# pag7936.net
KiCad netlist of a schematic drawn in Altium Designer
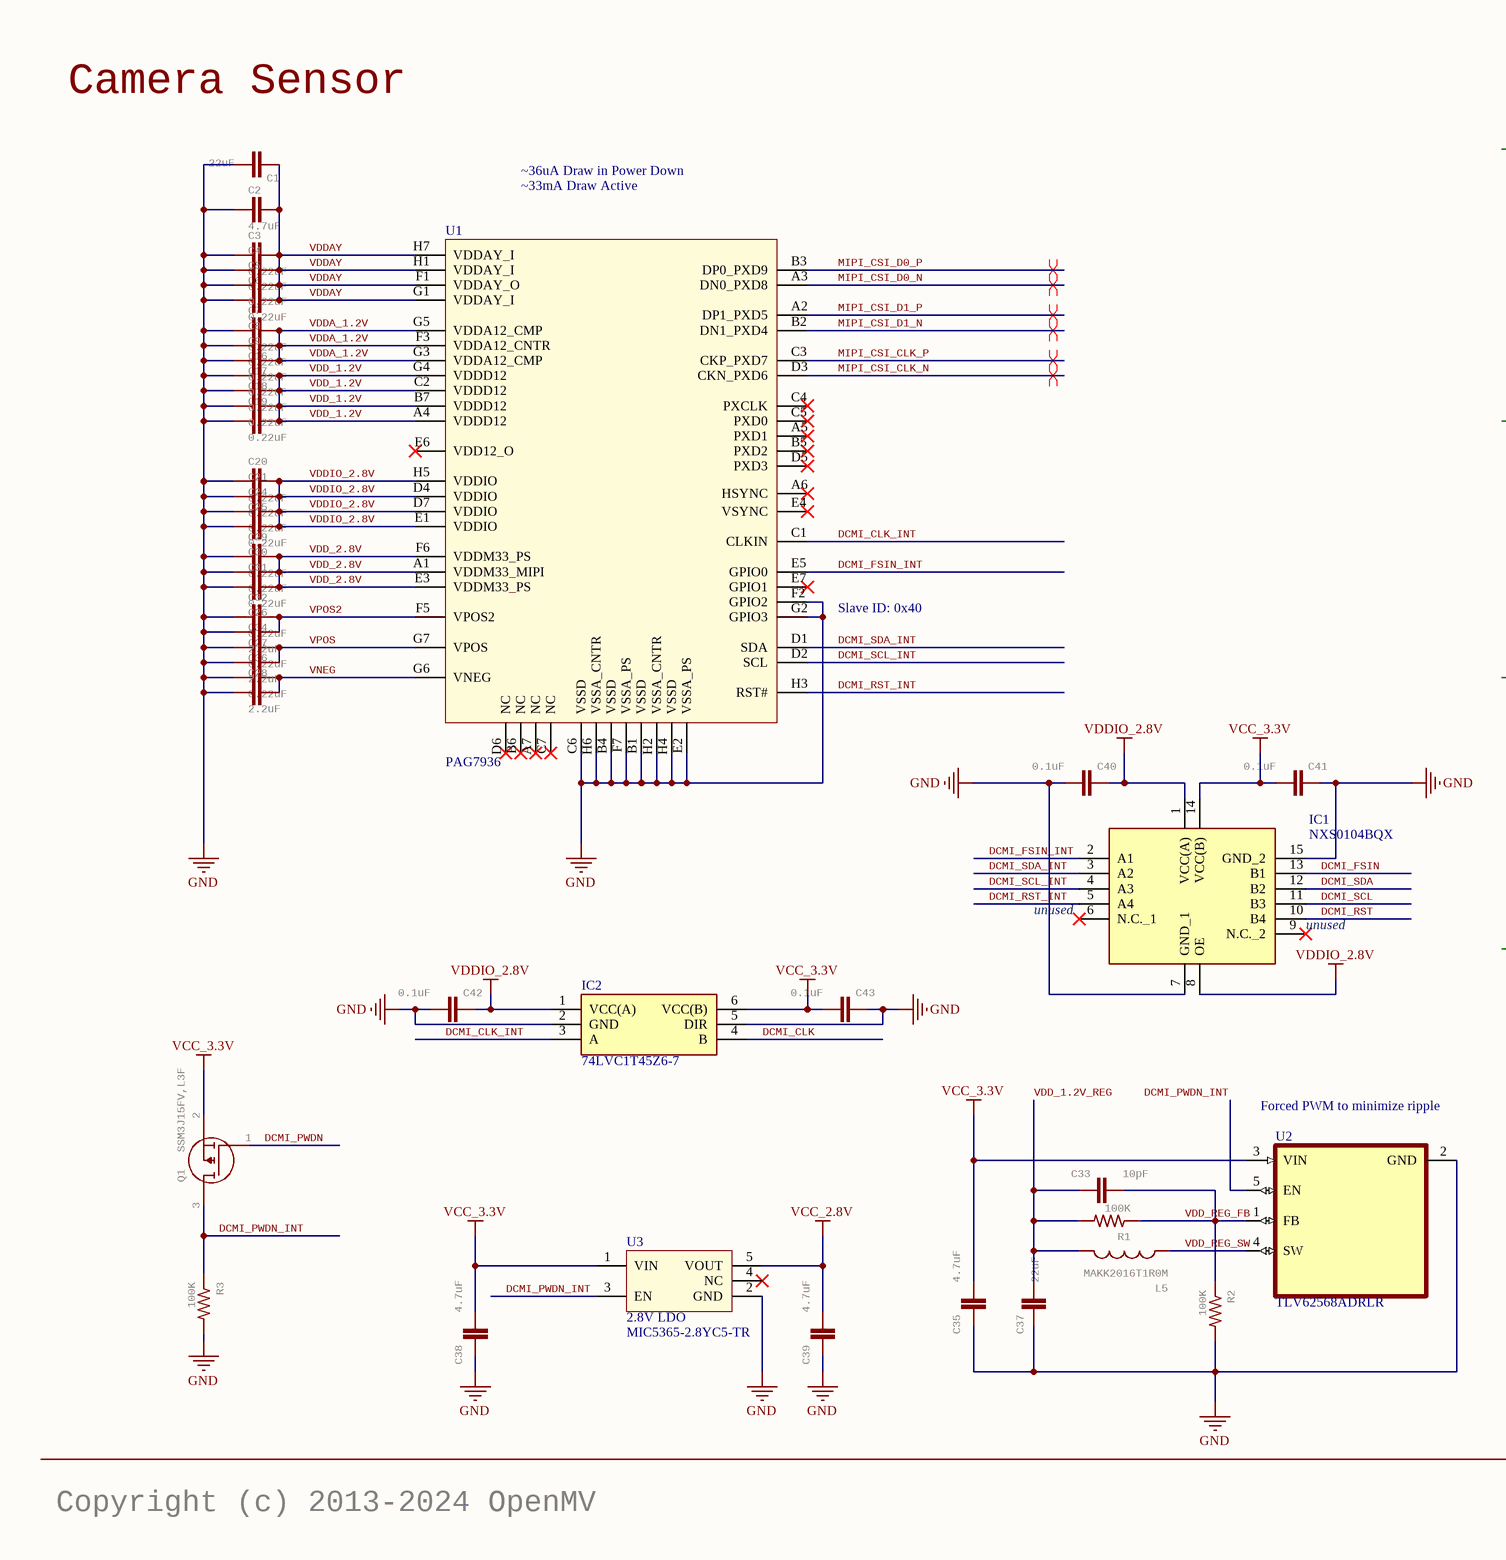
[diagram p0: pag7936.SchDoc, left]
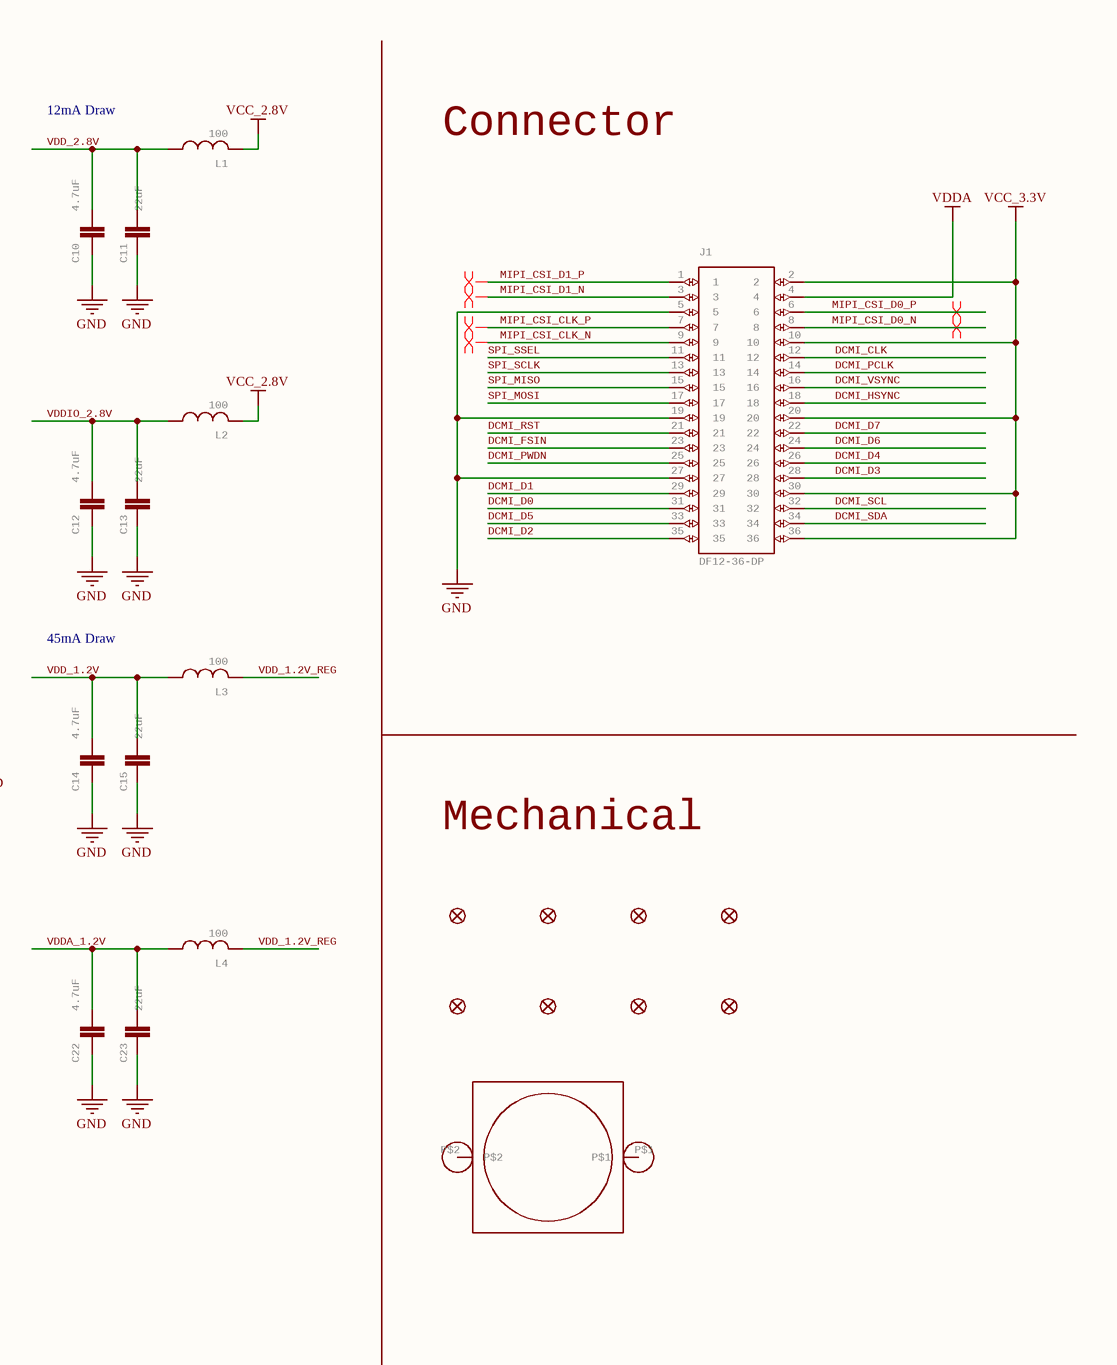
[diagram p1: pag7936.SchDoc, right]

(export (version "E")
  (design (tool "Eeschema 10.0.6"))
  (components
    (comp (ref "C1")
      (value "22uF")
      (footprint "0805")
      (fields (field (name "MPN") "CL21A226MQQNNNE"))
      (libsource (lib "") (part "22UF-0805-6.3V-20%_1"))
    )
    (comp (ref "C2")
      (value "4.7uF")
      (footprint "0402-CAP")
      (description "CapacitorStandard 0603 ceramic capacitor, and 0.1\" leaded capacitor.")
      (fields (field (name "MPN") "JMK105BBJ475MV-F"))
      (libsource (lib "openmv-ae3-r2") (part "CAP0402-CAP"))
    )
    (comp (ref "C3")
      (value "0.22uF")
      (footprint "C0201")
      (description "CAPACITOR, European symbol")
      (fields (field (name "MPN") "GRM033R60J224ME15D"))
      (libsource (lib "openmv-ae3-r2") (part "C-EUC0201"))
    )
    (comp (ref "C4")
      (value "0.22uF")
      (footprint "C0201")
      (description "CAPACITOR, European symbol")
      (fields (field (name "MPN") "GRM033R60J224ME15D"))
      (libsource (lib "openmv-ae3-r2") (part "C-EUC0201"))
    )
    (comp (ref "C5")
      (value "0.22uF")
      (footprint "C0201")
      (description "CAPACITOR, European symbol")
      (fields (field (name "MPN") "GRM033R60J224ME15D"))
      (libsource (lib "openmv-ae3-r2") (part "C-EUC0201"))
    )
    (comp (ref "C6")
      (value "0.22uF")
      (footprint "C0201")
      (description "CAPACITOR, European symbol")
      (fields (field (name "MPN") "GRM033R60J224ME15D"))
      (libsource (lib "openmv-ae3-r2") (part "C-EUC0201"))
    )
    (comp (ref "C7")
      (value "0.22uF")
      (footprint "C0201")
      (description "CAPACITOR, European symbol")
      (fields (field (name "MPN") "GRM033R60J224ME15D"))
      (libsource (lib "openmv-ae3-r2") (part "C-EUC0201"))
    )
    (comp (ref "C8")
      (value "0.22uF")
      (footprint "C0201")
      (description "CAPACITOR, European symbol")
      (fields (field (name "MPN") "GRM033R60J224ME15D"))
      (libsource (lib "openmv-ae3-r2") (part "C-EUC0201"))
    )
    (comp (ref "C9")
      (value "0.22uF")
      (footprint "C0201")
      (description "CAPACITOR, European symbol")
      (fields (field (name "MPN") "GRM033R60J224ME15D"))
      (libsource (lib "openmv-ae3-r2") (part "C-EUC0201"))
    )
    (comp (ref "C10")
      (value "4.7uF")
      (footprint "0402-CAP")
      (description "0402 (1005 Metric) Nick Garner - TeleSense")
      (fields (field (name "MPN") "JMK105BBJ475MV-F"))
      (libsource (lib "camera-modules") (part "CAP_0402"))
    )
    (comp (ref "C11")
      (value "22uF")
      (footprint "0805")
      (fields (field (name "MPN") "CL21A226MQQNNNE"))
      (libsource (lib "camera-modules") (part "22UF-0805-6.3V-20%"))
    )
    (comp (ref "C12")
      (value "4.7uF")
      (footprint "0402-CAP")
      (description "0402 (1005 Metric) Nick Garner - TeleSense")
      (fields (field (name "MPN") "JMK105BBJ475MV-F"))
      (libsource (lib "camera-modules") (part "CAP_0402"))
    )
    (comp (ref "C13")
      (value "22uF")
      (footprint "0805")
      (fields (field (name "MPN") "CL21A226MQQNNNE"))
      (libsource (lib "camera-modules") (part "22UF-0805-6.3V-20%"))
    )
    (comp (ref "C14")
      (value "4.7uF")
      (footprint "0402-CAP")
      (description "0402 (1005 Metric) Nick Garner - TeleSense")
      (fields (field (name "MPN") "JMK105BBJ475MV-F"))
      (libsource (lib "camera-modules") (part "CAP_0402"))
    )
    (comp (ref "C15")
      (value "22uF")
      (footprint "0805")
      (fields (field (name "MPN") "CL21A226MQQNNNE"))
      (libsource (lib "camera-modules") (part "22UF-0805-6.3V-20%"))
    )
    (comp (ref "C16")
      (value "0.22uF")
      (footprint "C0201")
      (description "CAPACITOR, European symbol")
      (fields (field (name "MPN") "GRM033R60J224ME15D"))
      (libsource (lib "openmv-ae3-r2") (part "C-EUC0201"))
    )
    (comp (ref "C17")
      (value "0.22uF")
      (footprint "C0201")
      (description "CAPACITOR, European symbol")
      (fields (field (name "MPN") "GRM033R60J224ME15D"))
      (libsource (lib "openmv-ae3-r2") (part "C-EUC0201"))
    )
    (comp (ref "C18")
      (value "0.22uF")
      (footprint "C0201")
      (description "CAPACITOR, European symbol")
      (fields (field (name "MPN") "GRM033R60J224ME15D"))
      (libsource (lib "openmv-ae3-r2") (part "C-EUC0201"))
    )
    (comp (ref "C19")
      (value "0.22uF")
      (footprint "C0201")
      (description "CAPACITOR, European symbol")
      (fields (field (name "MPN") "GRM033R60J224ME15D"))
      (libsource (lib "openmv-ae3-r2") (part "C-EUC0201"))
    )
    (comp (ref "C20")
      (value "0.22uF")
      (footprint "C0201")
      (description "CAPACITOR, European symbol")
      (fields (field (name "MPN") "GRM033R60J224ME15D"))
      (libsource (lib "openmv-ae3-r2") (part "C-EUC0201"))
    )
    (comp (ref "C21")
      (value "0.22uF")
      (footprint "C0201")
      (description "CAPACITOR, European symbol")
      (fields (field (name "MPN") "GRM033R60J224ME15D"))
      (libsource (lib "openmv-ae3-r2") (part "C-EUC0201"))
    )
    (comp (ref "C22")
      (value "4.7uF")
      (footprint "0402-CAP")
      (description "0402 (1005 Metric) Nick Garner - TeleSense")
      (fields (field (name "MPN") "JMK105BBJ475MV-F"))
      (libsource (lib "camera-modules") (part "CAP_0402"))
    )
    (comp (ref "C23")
      (value "22uF")
      (footprint "0805")
      (fields (field (name "MPN") "CL21A226MQQNNNE"))
      (libsource (lib "camera-modules") (part "22UF-0805-6.3V-20%"))
    )
    (comp (ref "C24")
      (value "0.22uF")
      (footprint "C0201")
      (description "CAPACITOR, European symbol")
      (fields (field (name "MPN") "GRM033R60J224ME15D"))
      (libsource (lib "openmv-ae3-r2") (part "C-EUC0201"))
    )
    (comp (ref "C25")
      (value "0.22uF")
      (footprint "C0201")
      (description "CAPACITOR, European symbol")
      (fields (field (name "MPN") "GRM033R60J224ME15D"))
      (libsource (lib "openmv-ae3-r2") (part "C-EUC0201"))
    )
    (comp (ref "C26")
      (value "2.2uF")
      (footprint "0402-CAP")
      (description "CapacitorStandard 0603 ceramic capacitor, and 0.1\" leaded capacitor.")
      (fields (field (name "MPN") "CL05A225MQ5NNNC"))
      (libsource (lib "openmv-ae3-r2") (part "CAP0402-CAP"))
    )
    (comp (ref "C27")
      (value "2.2uF")
      (footprint "0402-CAP")
      (description "CapacitorStandard 0603 ceramic capacitor, and 0.1\" leaded capacitor.")
      (fields (field (name "MPN") "CL05A225MQ5NNNC"))
      (libsource (lib "openmv-ae3-r2") (part "CAP0402-CAP"))
    )
    (comp (ref "C28")
      (value "2.2uF")
      (footprint "0402-CAP")
      (description "CapacitorStandard 0603 ceramic capacitor, and 0.1\" leaded capacitor.")
      (fields (field (name "MPN") "CL05A225MQ5NNNC"))
      (libsource (lib "openmv-ae3-r2") (part "CAP0402-CAP"))
    )
    (comp (ref "C29")
      (value "0.22uF")
      (footprint "C0201")
      (description "CAPACITOR, European symbol")
      (fields (field (name "MPN") "GRM033R60J224ME15D"))
      (libsource (lib "openmv-ae3-r2") (part "C-EUC0201"))
    )
    (comp (ref "C30")
      (value "0.22uF")
      (footprint "C0201")
      (description "CAPACITOR, European symbol")
      (fields (field (name "MPN") "GRM033R60J224ME15D"))
      (libsource (lib "openmv-ae3-r2") (part "C-EUC0201"))
    )
    (comp (ref "C31")
      (value "0.22uF")
      (footprint "C0201")
      (description "CAPACITOR, European symbol")
      (fields (field (name "MPN") "GRM033R60J224ME15D"))
      (libsource (lib "openmv-ae3-r2") (part "C-EUC0201"))
    )
    (comp (ref "C32")
      (value "0.22uF")
      (footprint "C0201")
      (description "CAPACITOR, European symbol")
      (fields (field (name "MPN") "GRM033R60J224ME15D"))
      (libsource (lib "openmv-ae3-r2") (part "C-EUC0201"))
    )
    (comp (ref "C33")
      (value "10pF")
      (footprint "0402-CAP")
      (description "0402 (1005 Metric) Nick Garner - TeleSense")
      (fields (field (name "MPN") "0402N100D500CT"))
      (libsource (lib "") (part "CAP_0402_1"))
    )
    (comp (ref "C34")
      (value "0.22uF")
      (footprint "C0201")
      (description "CAPACITOR, European symbol")
      (fields (field (name "MPN") "GRM033R60J224ME15D"))
      (libsource (lib "openmv-ae3-r2") (part "C-EUC0201"))
    )
    (comp (ref "C35")
      (value "4.7uF")
      (footprint "0402-CAP")
      (description "0402 (1005 Metric) Nick Garner - TeleSense")
      (fields (field (name "MPN") "JMK105BBJ475MV-F"))
      (libsource (lib "camera-modules") (part "CAP_0402"))
    )
    (comp (ref "C36")
      (value "0.22uF")
      (footprint "C0201")
      (description "CAPACITOR, European symbol")
      (fields (field (name "MPN") "GRM033R60J224ME15D"))
      (libsource (lib "openmv-ae3-r2") (part "C-EUC0201"))
    )
    (comp (ref "C37")
      (value "22uF")
      (footprint "0805")
      (fields (field (name "MPN") "CL21A226MQQNNNE"))
      (libsource (lib "camera-modules") (part "22UF-0805-6.3V-20%"))
    )
    (comp (ref "C38")
      (value "4.7uF")
      (footprint "0402-CAP")
      (description "0402 (1005 Metric) Nick Garner - TeleSense")
      (fields (field (name "MPN") "JMK105BBJ475MV-F"))
      (libsource (lib "openmv-ae3-r2") (part "CAP_0402"))
    )
    (comp (ref "C39")
      (value "4.7uF")
      (footprint "0402-CAP")
      (description "0402 (1005 Metric) Nick Garner - TeleSense")
      (fields (field (name "MPN") "JMK105BBJ475MV-F"))
      (libsource (lib "openmv-ae3-r2") (part "CAP_0402"))
    )
    (comp (ref "C40")
      (value "0.1uF")
      (footprint "0402-CAP")
      (description "CAPACITOR, European symbol")
      (fields (field (name "MPN") "C0402C104Z4VAC"))
      (libsource (lib "openmv-ae3") (part "C-EUC0201"))
    )
    (comp (ref "C41")
      (value "0.1uF")
      (footprint "0402-CAP")
      (description "CAPACITOR, European symbol")
      (fields (field (name "MPN") "C0402C104Z4VAC"))
      (libsource (lib "openmv-ae3") (part "C-EUC0201"))
    )
    (comp (ref "C42")
      (value "0.1uF")
      (footprint "0402-CAP")
      (description "CAPACITOR, European symbol")
      (fields (field (name "MPN") "C0402C104Z4VAC"))
      (libsource (lib "openmv-ae3") (part "C-EUC0201"))
    )
    (comp (ref "C43")
      (value "0.1uF")
      (footprint "0402-CAP")
      (description "CAPACITOR, European symbol")
      (fields (field (name "MPN") "C0402C104Z4VAC"))
      (libsource (lib "openmv-ae3") (part "C-EUC0201"))
    )
    (comp (ref "FD1")
      (value "FIDUCIAL1X2")
      (footprint "FIDUCIAL-1X2")
      (fields (field (name "LIBRARYNAME") "SparkFun-Aesthetics"))
      (libsource (lib "camera-modules") (part "FIDUCIAL1X2"))
    )
    (comp (ref "FD2")
      (value "FIDUCIAL1X2")
      (footprint "FIDUCIAL-1X2")
      (fields (field (name "LIBRARYNAME") "SparkFun-Aesthetics"))
      (libsource (lib "camera-modules") (part "FIDUCIAL1X2"))
    )
    (comp (ref "FD3")
      (value "FIDUCIAL1X2")
      (footprint "FIDUCIAL-1X2")
      (fields (field (name "LIBRARYNAME") "SparkFun-Aesthetics"))
      (libsource (lib "camera-modules") (part "FIDUCIAL1X2"))
    )
    (comp (ref "FD4")
      (value "FIDUCIAL1X2")
      (footprint "FIDUCIAL-1X2")
      (fields (field (name "LIBRARYNAME") "SparkFun-Aesthetics"))
      (libsource (lib "camera-modules") (part "FIDUCIAL1X2"))
    )
    (comp (ref "FD5")
      (value "FIDUCIAL1X2")
      (footprint "FIDUCIAL-1X2")
      (fields (field (name "LIBRARYNAME") "SparkFun-Aesthetics"))
      (libsource (lib "camera-modules") (part "FIDUCIAL1X2"))
    )
    (comp (ref "FD6")
      (value "FIDUCIAL1X2")
      (footprint "FIDUCIAL-1X2")
      (fields (field (name "LIBRARYNAME") "SparkFun-Aesthetics"))
      (libsource (lib "camera-modules") (part "FIDUCIAL1X2"))
    )
    (comp (ref "FD7")
      (value "FIDUCIAL1X2")
      (footprint "FIDUCIAL-1X2")
      (fields (field (name "LIBRARYNAME") "SparkFun-Aesthetics"))
      (libsource (lib "camera-modules") (part "FIDUCIAL1X2"))
    )
    (comp (ref "FD8")
      (value "FIDUCIAL1X2")
      (footprint "FIDUCIAL-1X2")
      (fields (field (name "LIBRARYNAME") "SparkFun-Aesthetics"))
      (libsource (lib "camera-modules") (part "FIDUCIAL1X2"))
    )
    (comp (ref "H1")
      (value "LENSMOUNT20MM")
      (footprint "LENSMOUNT-20MM")
      (libsource (lib "camera-modules") (part "LENSMOUNT20MM"))
    )
    (comp (ref "IC1")
      (value "NXS0104BQX")
      (footprint "NXS0104BQX")
      (description "NXS0104 - Dual supply translating transceiver; open drain; autodirectionsensing@en-us")
      (fields (field (name "MOUSER PART NUMBER") "771-NXS0104BQX"))
      (libsource (lib "OpenMV, LLC") (part "NXS0104BQX"))
    )
    (comp (ref "IC2")
      (value "74LVC1T45Z6-7")
      (footprint "74LVC1T45Z67")
      (description "Integrated Circuit")
      (fields (field (name "MOUSER PART NUMBER") "621-74LVC1T45Z6-7"))
      (libsource (lib "*") (part "74LVC1T45Z6-7"))
    )
    (comp (ref "J1")
      (value "DF12-36-DP")
      (footprint "DF12-36-DP")
      (fields (field (name "MPN") "DF12NB(3.0)-36DP-0.5V(51)"))
      (libsource (lib "camera-modules") (part "DF12-36-DP"))
    )
    (comp (ref "L1")
      (value "100")
      (footprint "0402")
      (fields (field (name "MPN") "MFBM1V1005-101-R"))
      (libsource (lib "camera-modules") (part "INDUCTOR_0402"))
    )
    (comp (ref "L2")
      (value "100")
      (footprint "0402")
      (fields (field (name "MPN") "MFBM1V1005-101-R"))
      (libsource (lib "camera-modules") (part "INDUCTOR_0402"))
    )
    (comp (ref "L3")
      (value "100")
      (footprint "0402")
      (fields (field (name "MPN") "MFBM1V1005-101-R"))
      (libsource (lib "camera-modules") (part "INDUCTOR_0402"))
    )
    (comp (ref "L4")
      (value "100")
      (footprint "0402")
      (fields (field (name "MPN") "MFBM1V1005-101-R"))
      (libsource (lib "camera-modules") (part "INDUCTOR_0402"))
    )
    (comp (ref "L5")
      (value "MAKK2016T1R0M")
      (footprint "INDC2016X100N")
      (description "Ind Power Wirewound 1uH 20% 2MHz Metal 2200mA 0806 Check availability")
      (fields (field (name "MF") "Taiyo Yuden"))
      (libsource (lib "rt10") (part "MAKK2016T1R0M"))
    )
    (comp (ref "Q1")
      (value "SSM3J15FV,L3F")
      (footprint "SSM3J15FV")
      (description "MOSFET 30 V, P-channel Trench MOSFET   Source:  Datasheet")
      (libsource (lib "camera-modules") (part "PMXB120EPEZ"))
    )
    (comp (ref "R1")
      (value "100K")
      (footprint "R0402")
      (description "RESISTOR, American symbol")
      (fields (field (name "MPN") "AC0402FR-07100KL"))
      (libsource (lib "camera-modules") (part "R-US_R0402"))
    )
    (comp (ref "R2")
      (value "100K")
      (footprint "R0402")
      (description "RESISTOR, American symbol")
      (fields (field (name "MPN") "AC0402FR-07100KL"))
      (libsource (lib "camera-modules") (part "R-US_R0402"))
    )
    (comp (ref "R3")
      (value "100K")
      (footprint "R0402")
      (description "RESISTOR, American symbol")
      (fields (field (name "MPN") "AC0402FR-07100KL"))
      (libsource (lib "camera-modules") (part "R-US_R0402"))
    )
    (comp (ref "U1")
      (value "PAG7936")
      (footprint "PAG7936")
      (fields (field (name "MF") "PixArt") (field (name "MPN") "PAG7936"))
      (libsource (lib "openmv-ae3-r2") (part "PAG7936"))
    )
    (comp (ref "U2")
      (value "TLV62568ADRLR")
      (footprint "SOT50P160X60-6N")
      (fields (field (name "MF") "Texas Instruments"))
      (libsource (lib "OpenMV, LLC") (part "TLV62568ADRLR"))
    )
    (comp (ref "U3")
      (value "2.8V LDO")
      (footprint "SC70-5")
      (fields
        (field (name "MF") "Microchip")
        (field (name "MPN") "MIC5365-2.8YC5-TR")
        (field (name "PART NUMBER") "MIC5365-2.8YC5-TR")
      )
      (libsource (lib "openmv-n6") (part "MIC5365-3.3YC5-TR"))
    )
  )
  (nets
    (net (code "1") (name "/DCMI_CLK") (class "Default")
      (node (ref "IC2") (pin "4") (pinfunction "B_4") (pintype "passive"))
      (node (ref "J1") (pin "12") (pinfunction "12_12") (pintype "bidirectional"))
    )
    (net (code "2") (name "/DCMI_CLK_INT") (class "Default")
      (node (ref "IC2") (pin "3") (pinfunction "A_3") (pintype "passive"))
      (node (ref "U1") (pin "C1") (pinfunction "CLKIN_C1") (pintype "passive"))
    )
    (net (code "3") (name "/DCMI_D0") (class "Default")
      (node (ref "J1") (pin "31") (pinfunction "31_31") (pintype "bidirectional"))
    )
    (net (code "4") (name "/DCMI_D1") (class "Default")
      (node (ref "J1") (pin "29") (pinfunction "29_29") (pintype "bidirectional"))
    )
    (net (code "5") (name "/DCMI_D2") (class "Default")
      (node (ref "J1") (pin "35") (pinfunction "35_35") (pintype "bidirectional"))
    )
    (net (code "6") (name "/DCMI_D3") (class "Default")
      (node (ref "J1") (pin "28") (pinfunction "28_28") (pintype "bidirectional"))
    )
    (net (code "7") (name "/DCMI_D4") (class "Default")
      (node (ref "J1") (pin "26") (pinfunction "26_26") (pintype "bidirectional"))
    )
    (net (code "8") (name "/DCMI_D5") (class "Default")
      (node (ref "J1") (pin "33") (pinfunction "33_33") (pintype "bidirectional"))
    )
    (net (code "9") (name "/DCMI_D6") (class "Default")
      (node (ref "J1") (pin "24") (pinfunction "24_24") (pintype "bidirectional"))
    )
    (net (code "10") (name "/DCMI_D7") (class "Default")
      (node (ref "J1") (pin "22") (pinfunction "22_22") (pintype "bidirectional"))
    )
    (net (code "11") (name "/DCMI_FSIN") (class "Default")
      (node (ref "IC1") (pin "13") (pinfunction "B1_13") (pintype "passive"))
      (node (ref "J1") (pin "23") (pinfunction "23_23") (pintype "bidirectional"))
    )
    (net (code "12") (name "/DCMI_FSIN_INT") (class "Default")
      (node (ref "IC1") (pin "2") (pinfunction "A1_2") (pintype "passive"))
      (node (ref "U1") (pin "E5") (pinfunction "GPIO0_E5") (pintype "passive"))
    )
    (net (code "13") (name "/DCMI_HSYNC") (class "Default")
      (node (ref "J1") (pin "18") (pinfunction "18_18") (pintype "bidirectional"))
    )
    (net (code "14") (name "/DCMI_PCLK") (class "Default")
      (node (ref "J1") (pin "14") (pinfunction "14_14") (pintype "bidirectional"))
    )
    (net (code "15") (name "/DCMI_PWDN") (class "Default")
      (node (ref "J1") (pin "25") (pinfunction "25_25") (pintype "bidirectional"))
      (node (ref "Q1") (pin "1") (pinfunction "G_1") (pintype "bidirectional"))
    )
    (net (code "16") (name "/DCMI_PWDN_INT") (class "Default")
      (node (ref "Q1") (pin "3") (pinfunction "D_3") (pintype "bidirectional"))
      (node (ref "R3") (pin "1") (pinfunction "1_1") (pintype "passive"))
      (node (ref "U2") (pin "5") (pinfunction "EN_5") (pintype "bidirectional"))
      (node (ref "U3") (pin "3") (pinfunction "EN_3") (pintype "passive"))
    )
    (net (code "17") (name "/DCMI_RST") (class "Default")
      (node (ref "IC1") (pin "10") (pinfunction "B4_10") (pintype "passive"))
      (node (ref "J1") (pin "21") (pinfunction "21_21") (pintype "bidirectional"))
    )
    (net (code "18") (name "/DCMI_RST_INT") (class "Default")
      (node (ref "IC1") (pin "5") (pinfunction "A4_5") (pintype "passive"))
      (node (ref "U1") (pin "H3") (pinfunction "RST#_H3") (pintype "passive"))
    )
    (net (code "19") (name "/DCMI_SCL") (class "Default")
      (node (ref "IC1") (pin "11") (pinfunction "B3_11") (pintype "passive"))
      (node (ref "J1") (pin "32") (pinfunction "32_32") (pintype "bidirectional"))
    )
    (net (code "20") (name "/DCMI_SCL_INT") (class "Default")
      (node (ref "IC1") (pin "4") (pinfunction "A3_4") (pintype "passive"))
      (node (ref "U1") (pin "D2") (pinfunction "SCL_D2") (pintype "passive"))
    )
    (net (code "21") (name "/DCMI_SDA") (class "Default")
      (node (ref "IC1") (pin "12") (pinfunction "B2_12") (pintype "passive"))
      (node (ref "J1") (pin "34") (pinfunction "34_34") (pintype "bidirectional"))
    )
    (net (code "22") (name "/DCMI_SDA_INT") (class "Default")
      (node (ref "IC1") (pin "3") (pinfunction "A2_3") (pintype "passive"))
      (node (ref "U1") (pin "D1") (pinfunction "SDA_D1") (pintype "passive"))
    )
    (net (code "23") (name "/DCMI_VSYNC") (class "Default")
      (node (ref "J1") (pin "16") (pinfunction "16_16") (pintype "bidirectional"))
    )
    (net (code "24") (name "/MIPI_CSI_CLK_N") (class "Default")
      (node (ref "J1") (pin "9") (pinfunction "9_9") (pintype "bidirectional"))
      (node (ref "U1") (pin "D3") (pinfunction "CKN_PXD6_D3") (pintype "passive"))
    )
    (net (code "25") (name "/MIPI_CSI_CLK_P") (class "Default")
      (node (ref "J1") (pin "7") (pinfunction "7_7") (pintype "bidirectional"))
      (node (ref "U1") (pin "C3") (pinfunction "CKP_PXD7_C3") (pintype "passive"))
    )
    (net (code "26") (name "/MIPI_CSI_D0_N") (class "Default")
      (node (ref "J1") (pin "8") (pinfunction "8_8") (pintype "bidirectional"))
      (node (ref "U1") (pin "A3") (pinfunction "DN0_PXD8_A3") (pintype "passive"))
    )
    (net (code "27") (name "/MIPI_CSI_D0_P") (class "Default")
      (node (ref "J1") (pin "6") (pinfunction "6_6") (pintype "bidirectional"))
      (node (ref "U1") (pin "B3") (pinfunction "DP0_PXD9_B3") (pintype "passive"))
    )
    (net (code "28") (name "/MIPI_CSI_D1_N") (class "Default")
      (node (ref "J1") (pin "3") (pinfunction "3_3") (pintype "bidirectional"))
      (node (ref "U1") (pin "B2") (pinfunction "DN1_PXD4_B2") (pintype "passive"))
    )
    (net (code "29") (name "/MIPI_CSI_D1_P") (class "Default")
      (node (ref "J1") (pin "1") (pinfunction "1_1") (pintype "bidirectional"))
      (node (ref "U1") (pin "A2") (pinfunction "DP1_PXD5_A2") (pintype "passive"))
    )
    (net (code "30") (name "/SPI_MISO") (class "Default")
      (node (ref "J1") (pin "15") (pinfunction "15_15") (pintype "bidirectional"))
    )
    (net (code "31") (name "/SPI_MOSI") (class "Default")
      (node (ref "J1") (pin "17") (pinfunction "17_17") (pintype "bidirectional"))
    )
    (net (code "32") (name "/SPI_SCLK") (class "Default")
      (node (ref "J1") (pin "13") (pinfunction "13_13") (pintype "bidirectional"))
    )
    (net (code "33") (name "/SPI_SSEL") (class "Default")
      (node (ref "J1") (pin "11") (pinfunction "11_11") (pintype "bidirectional"))
    )
    (net (code "34") (name "/VDDAY") (class "Default")
      (node (ref "C1") (pin "1") (pinfunction "1_1") (pintype "passive"))
      (node (ref "C2") (pin "1") (pinfunction "1_1") (pintype "passive"))
      (node (ref "C3") (pin "2") (pinfunction "2_2") (pintype "passive"))
      (node (ref "C4") (pin "2") (pinfunction "2_2") (pintype "passive"))
      (node (ref "C5") (pin "2") (pinfunction "2_2") (pintype "passive"))
      (node (ref "C6") (pin "2") (pinfunction "2_2") (pintype "passive"))
      (node (ref "U1") (pin "F1") (pinfunction "VDDAY_O_F1") (pintype "passive"))
      (node (ref "U1") (pin "G1") (pinfunction "VDDAY_I_G1") (pintype "passive"))
      (node (ref "U1") (pin "H1") (pinfunction "VDDAY_I_H1") (pintype "passive"))
      (node (ref "U1") (pin "H7") (pinfunction "VDDAY_I_H7") (pintype "passive"))
    )
    (net (code "35") (name "/VDDA_1.2V") (class "Default")
      (node (ref "C22") (pin "2") (pinfunction "2_2") (pintype "passive"))
      (node (ref "C23") (pin "2") (pinfunction "2_2") (pintype "passive"))
      (node (ref "C7") (pin "2") (pinfunction "2_2") (pintype "passive"))
      (node (ref "C8") (pin "2") (pinfunction "2_2") (pintype "passive"))
      (node (ref "C9") (pin "2") (pinfunction "2_2") (pintype "passive"))
      (node (ref "L4") (pin "1") (pinfunction "P$1_1") (pintype "passive"))
      (node (ref "U1") (pin "F3") (pinfunction "VDDA12_CNTR_F3") (pintype "passive"))
      (node (ref "U1") (pin "G3") (pinfunction "VDDA12_CMP_G3") (pintype "passive"))
      (node (ref "U1") (pin "G5") (pinfunction "VDDA12_CMP_G5") (pintype "passive"))
    )
    (net (code "36") (name "/VDD_1.2V") (class "Default")
      (node (ref "C14") (pin "2") (pinfunction "2_2") (pintype "passive"))
      (node (ref "C15") (pin "2") (pinfunction "2_2") (pintype "passive"))
      (node (ref "C16") (pin "2") (pinfunction "2_2") (pintype "passive"))
      (node (ref "C17") (pin "2") (pinfunction "2_2") (pintype "passive"))
      (node (ref "C18") (pin "2") (pinfunction "2_2") (pintype "passive"))
      (node (ref "C19") (pin "2") (pinfunction "2_2") (pintype "passive"))
      (node (ref "L3") (pin "1") (pinfunction "P$1_1") (pintype "passive"))
      (node (ref "U1") (pin "A4") (pinfunction "VDDD12_A4") (pintype "passive"))
      (node (ref "U1") (pin "B7") (pinfunction "VDDD12_B7") (pintype "passive"))
      (node (ref "U1") (pin "C2") (pinfunction "VDDD12_C2") (pintype "passive"))
      (node (ref "U1") (pin "G4") (pinfunction "VDDD12_G4") (pintype "passive"))
    )
    (net (code "37") (name "/VDD_1.2V_REG") (class "Default")
      (node (ref "C33") (pin "1") (pinfunction "1_1") (pintype "passive"))
      (node (ref "C37") (pin "2") (pinfunction "2_2") (pintype "passive"))
      (node (ref "L3") (pin "2") (pinfunction "P$2_2") (pintype "passive"))
      (node (ref "L4") (pin "2") (pinfunction "P$2_2") (pintype "passive"))
      (node (ref "L5") (pin "2") (pinfunction "2_2") (pintype "passive"))
      (node (ref "R1") (pin "2") (pinfunction "2_2") (pintype "passive"))
    )
    (net (code "38") (name "/VDD_2.8V") (class "Default")
      (node (ref "C10") (pin "2") (pinfunction "2_2") (pintype "passive"))
      (node (ref "C11") (pin "2") (pinfunction "2_2") (pintype "passive"))
      (node (ref "C29") (pin "2") (pinfunction "2_2") (pintype "passive"))
      (node (ref "C30") (pin "2") (pinfunction "2_2") (pintype "passive"))
      (node (ref "C31") (pin "2") (pinfunction "2_2") (pintype "passive"))
      (node (ref "L1") (pin "1") (pinfunction "P$1_1") (pintype "passive"))
      (node (ref "U1") (pin "A1") (pinfunction "VDDM33_MIPI_A1") (pintype "passive"))
      (node (ref "U1") (pin "E3") (pinfunction "VDDM33_PS_E3") (pintype "passive"))
      (node (ref "U1") (pin "F6") (pinfunction "VDDM33_PS_F6") (pintype "passive"))
    )
    (net (code "39") (name "/VDD_REG_FB") (class "Default")
      (node (ref "C33") (pin "2") (pinfunction "2_2") (pintype "passive"))
      (node (ref "R1") (pin "1") (pinfunction "1_1") (pintype "passive"))
      (node (ref "R2") (pin "1") (pinfunction "1_1") (pintype "passive"))
      (node (ref "U2") (pin "1") (pinfunction "FB_1") (pintype "bidirectional"))
    )
    (net (code "40") (name "/VDD_REG_SW") (class "Default")
      (node (ref "L5") (pin "1") (pinfunction "1_1") (pintype "passive"))
      (node (ref "U2") (pin "4") (pinfunction "SW_4") (pintype "bidirectional"))
    )
    (net (code "41") (name "/VNEG") (class "Default")
      (node (ref "C28") (pin "1") (pinfunction "1_1") (pintype "passive"))
      (node (ref "C36") (pin "2") (pinfunction "2_2") (pintype "passive"))
      (node (ref "U1") (pin "G6") (pinfunction "VNEG_G6") (pintype "passive"))
    )
    (net (code "42") (name "/VPOS") (class "Default")
      (node (ref "C27") (pin "1") (pinfunction "1_1") (pintype "passive"))
      (node (ref "C34") (pin "2") (pinfunction "2_2") (pintype "passive"))
      (node (ref "U1") (pin "G7") (pinfunction "VPOS_G7") (pintype "passive"))
    )
    (net (code "43") (name "/VPOS2") (class "Default")
      (node (ref "C26") (pin "1") (pinfunction "1_1") (pintype "passive"))
      (node (ref "C32") (pin "2") (pinfunction "2_2") (pintype "passive"))
      (node (ref "U1") (pin "F5") (pinfunction "VPOS2_F5") (pintype "passive"))
    )
    (net (code "44") (name "GND") (class "Default")
      (node (ref "C1") (pin "2") (pinfunction "2_2") (pintype "passive"))
      (node (ref "C10") (pin "1") (pinfunction "1_1") (pintype "passive"))
      (node (ref "C11") (pin "1") (pinfunction "1_1") (pintype "passive"))
      (node (ref "C12") (pin "1") (pinfunction "1_1") (pintype "passive"))
      (node (ref "C13") (pin "1") (pinfunction "1_1") (pintype "passive"))
      (node (ref "C14") (pin "1") (pinfunction "1_1") (pintype "passive"))
      (node (ref "C15") (pin "1") (pinfunction "1_1") (pintype "passive"))
      (node (ref "C16") (pin "1") (pinfunction "1_1") (pintype "passive"))
      (node (ref "C17") (pin "1") (pinfunction "1_1") (pintype "passive"))
      (node (ref "C18") (pin "1") (pinfunction "1_1") (pintype "passive"))
      (node (ref "C19") (pin "1") (pinfunction "1_1") (pintype "passive"))
      (node (ref "C2") (pin "2") (pinfunction "2_2") (pintype "passive"))
      (node (ref "C20") (pin "1") (pinfunction "1_1") (pintype "passive"))
      (node (ref "C21") (pin "1") (pinfunction "1_1") (pintype "passive"))
      (node (ref "C22") (pin "1") (pinfunction "1_1") (pintype "passive"))
      (node (ref "C23") (pin "1") (pinfunction "1_1") (pintype "passive"))
      (node (ref "C24") (pin "1") (pinfunction "1_1") (pintype "passive"))
      (node (ref "C25") (pin "1") (pinfunction "1_1") (pintype "passive"))
      (node (ref "C26") (pin "2") (pinfunction "2_2") (pintype "passive"))
      (node (ref "C27") (pin "2") (pinfunction "2_2") (pintype "passive"))
      (node (ref "C28") (pin "2") (pinfunction "2_2") (pintype "passive"))
      (node (ref "C29") (pin "1") (pinfunction "1_1") (pintype "passive"))
      (node (ref "C3") (pin "1") (pinfunction "1_1") (pintype "passive"))
      (node (ref "C30") (pin "1") (pinfunction "1_1") (pintype "passive"))
      (node (ref "C31") (pin "1") (pinfunction "1_1") (pintype "passive"))
      (node (ref "C32") (pin "1") (pinfunction "1_1") (pintype "passive"))
      (node (ref "C34") (pin "1") (pinfunction "1_1") (pintype "passive"))
      (node (ref "C35") (pin "1") (pinfunction "1_1") (pintype "passive"))
      (node (ref "C36") (pin "1") (pinfunction "1_1") (pintype "passive"))
      (node (ref "C37") (pin "1") (pinfunction "1_1") (pintype "passive"))
      (node (ref "C38") (pin "1") (pinfunction "1_1") (pintype "passive"))
      (node (ref "C39") (pin "1") (pinfunction "1_1") (pintype "passive"))
      (node (ref "C4") (pin "1") (pinfunction "1_1") (pintype "passive"))
      (node (ref "C40") (pin "2") (pinfunction "2_2") (pintype "passive"))
      (node (ref "C41") (pin "1") (pinfunction "1_1") (pintype "passive"))
      (node (ref "C42") (pin "2") (pinfunction "2_2") (pintype "passive"))
      (node (ref "C43") (pin "1") (pinfunction "1_1") (pintype "passive"))
      (node (ref "C5") (pin "1") (pinfunction "1_1") (pintype "passive"))
      (node (ref "C6") (pin "1") (pinfunction "1_1") (pintype "passive"))
      (node (ref "C7") (pin "1") (pinfunction "1_1") (pintype "passive"))
      (node (ref "C8") (pin "1") (pinfunction "1_1") (pintype "passive"))
      (node (ref "C9") (pin "1") (pinfunction "1_1") (pintype "passive"))
      (node (ref "IC1") (pin "15") (pinfunction "GND_2_15") (pintype "passive"))
      (node (ref "IC1") (pin "7") (pinfunction "GND_1_7") (pintype "passive"))
      (node (ref "IC2") (pin "2") (pinfunction "GND_2") (pintype "passive"))
      (node (ref "IC2") (pin "5") (pinfunction "DIR_5") (pintype "passive"))
      (node (ref "J1") (pin "19") (pinfunction "19_19") (pintype "bidirectional"))
      (node (ref "J1") (pin "27") (pinfunction "27_27") (pintype "bidirectional"))
      (node (ref "J1") (pin "5") (pinfunction "5_5") (pintype "bidirectional"))
      (node (ref "R2") (pin "2") (pinfunction "2_2") (pintype "passive"))
      (node (ref "R3") (pin "2") (pinfunction "2_2") (pintype "passive"))
      (node (ref "U1") (pin "B1") (pinfunction "VSSD_B1") (pintype "passive"))
      (node (ref "U1") (pin "B4") (pinfunction "VSSD_B4") (pintype "passive"))
      (node (ref "U1") (pin "C6") (pinfunction "VSSD_C6") (pintype "passive"))
      (node (ref "U1") (pin "E2") (pinfunction "VSSA_PS_E2") (pintype "passive"))
      (node (ref "U1") (pin "F2") (pinfunction "GPIO2_F2") (pintype "passive"))
      (node (ref "U1") (pin "F7") (pinfunction "VSSA_PS_F7") (pintype "passive"))
      (node (ref "U1") (pin "G2") (pinfunction "GPIO3_G2") (pintype "passive"))
      (node (ref "U1") (pin "H2") (pinfunction "VSSA_CNTR_H2") (pintype "passive"))
      (node (ref "U1") (pin "H4") (pinfunction "VSSD_H4") (pintype "passive"))
      (node (ref "U1") (pin "H6") (pinfunction "VSSA_CNTR_H6") (pintype "passive"))
      (node (ref "U2") (pin "2") (pinfunction "GND_2") (pintype "power_in"))
      (node (ref "U3") (pin "2") (pinfunction "GND_2") (pintype "passive"))
    )
    (net (code "45") (name "VCC_2.8V") (class "Default")
      (node (ref "C39") (pin "2") (pinfunction "2_2") (pintype "passive"))
      (node (ref "L1") (pin "2") (pinfunction "P$2_2") (pintype "passive"))
      (node (ref "L2") (pin "2") (pinfunction "P$2_2") (pintype "passive"))
      (node (ref "U3") (pin "5") (pinfunction "VOUT_5") (pintype "passive"))
    )
    (net (code "46") (name "VCC_3.3V") (class "Default")
      (node (ref "C35") (pin "2") (pinfunction "2_2") (pintype "passive"))
      (node (ref "C38") (pin "2") (pinfunction "2_2") (pintype "passive"))
      (node (ref "C41") (pin "2") (pinfunction "2_2") (pintype "passive"))
      (node (ref "C43") (pin "2") (pinfunction "2_2") (pintype "passive"))
      (node (ref "IC1") (pin "14") (pinfunction "VCC(B)_14") (pintype "passive"))
      (node (ref "IC2") (pin "6") (pinfunction "VCC(B)_6") (pintype "passive"))
      (node (ref "J1") (pin "10") (pinfunction "10_10") (pintype "bidirectional"))
      (node (ref "J1") (pin "2") (pinfunction "2_2") (pintype "bidirectional"))
      (node (ref "J1") (pin "20") (pinfunction "20_20") (pintype "bidirectional"))
      (node (ref "J1") (pin "30") (pinfunction "30_30") (pintype "bidirectional"))
      (node (ref "J1") (pin "36") (pinfunction "36_36") (pintype "bidirectional"))
      (node (ref "Q1") (pin "2") (pinfunction "S_2") (pintype "bidirectional"))
      (node (ref "U2") (pin "3") (pinfunction "VIN_3") (pintype "input"))
      (node (ref "U3") (pin "1") (pinfunction "VIN_1") (pintype "passive"))
    )
    (net (code "47") (name "VDDA") (class "Default")
      (node (ref "J1") (pin "4") (pinfunction "4_4") (pintype "bidirectional"))
    )
    (net (code "48") (name "VDDIO_2.8V") (class "Default")
      (node (ref "C12") (pin "2") (pinfunction "2_2") (pintype "passive"))
      (node (ref "C13") (pin "2") (pinfunction "2_2") (pintype "passive"))
      (node (ref "C20") (pin "2") (pinfunction "2_2") (pintype "passive"))
      (node (ref "C21") (pin "2") (pinfunction "2_2") (pintype "passive"))
      (node (ref "C24") (pin "2") (pinfunction "2_2") (pintype "passive"))
      (node (ref "C25") (pin "2") (pinfunction "2_2") (pintype "passive"))
      (node (ref "C40") (pin "1") (pinfunction "1_1") (pintype "passive"))
      (node (ref "C42") (pin "1") (pinfunction "1_1") (pintype "passive"))
      (node (ref "IC1") (pin "1") (pinfunction "VCC(A)_1") (pintype "passive"))
      (node (ref "IC1") (pin "8") (pinfunction "OE_8") (pintype "passive"))
      (node (ref "IC2") (pin "1") (pinfunction "VCC(A)_1") (pintype "passive"))
      (node (ref "L2") (pin "1") (pinfunction "P$1_1") (pintype "passive"))
      (node (ref "U1") (pin "D4") (pinfunction "VDDIO_D4") (pintype "passive"))
      (node (ref "U1") (pin "D7") (pinfunction "VDDIO_D7") (pintype "passive"))
      (node (ref "U1") (pin "E1") (pinfunction "VDDIO_E1") (pintype "passive"))
      (node (ref "U1") (pin "H5") (pinfunction "VDDIO_H5") (pintype "passive"))
    )
    (net (code "49") (name "unconnected-(H1-PadP$1)") (class "Default")
      (node (ref "H1") (pin "P$1") (pinfunction "P$1_P$1") (pintype "power_in"))
    )
    (net (code "50") (name "unconnected-(H1-PadP$2)") (class "Default")
      (node (ref "H1") (pin "P$2") (pinfunction "P$2_P$2") (pintype "power_in"))
    )
    (net (code "51") (name "unconnected-(IC1-N.C._1-Pad6)") (class "Default")
      (node (ref "IC1") (pin "6") (pinfunction "N.C._1_6") (pintype "passive+no_connect"))
    )
    (net (code "52") (name "unconnected-(IC1-N.C._2-Pad9)") (class "Default")
      (node (ref "IC1") (pin "9") (pinfunction "N.C._2_9") (pintype "passive+no_connect"))
    )
    (net (code "53") (name "unconnected-(U1-GPIO1-PadE7)") (class "Default")
      (node (ref "U1") (pin "E7") (pinfunction "GPIO1_E7") (pintype "passive+no_connect"))
    )
    (net (code "54") (name "unconnected-(U1-HSYNC-PadA6)") (class "Default")
      (node (ref "U1") (pin "A6") (pinfunction "HSYNC_A6") (pintype "passive+no_connect"))
    )
    (net (code "55") (name "unconnected-(U1-NC-PadA7)") (class "Default")
      (node (ref "U1") (pin "A7") (pinfunction "NC_A7") (pintype "passive+no_connect"))
    )
    (net (code "56") (name "unconnected-(U1-NC-PadB6)") (class "Default")
      (node (ref "U1") (pin "B6") (pinfunction "NC_B6") (pintype "passive+no_connect"))
    )
    (net (code "57") (name "unconnected-(U1-NC-PadC7)") (class "Default")
      (node (ref "U1") (pin "C7") (pinfunction "NC_C7") (pintype "passive+no_connect"))
    )
    (net (code "58") (name "unconnected-(U1-NC-PadD6)") (class "Default")
      (node (ref "U1") (pin "D6") (pinfunction "NC_D6") (pintype "passive+no_connect"))
    )
    (net (code "59") (name "unconnected-(U1-PXCLK-PadC4)") (class "Default")
      (node (ref "U1") (pin "C4") (pinfunction "PXCLK_C4") (pintype "passive+no_connect"))
    )
    (net (code "60") (name "unconnected-(U1-PXD0-PadC5)") (class "Default")
      (node (ref "U1") (pin "C5") (pinfunction "PXD0_C5") (pintype "passive+no_connect"))
    )
    (net (code "61") (name "unconnected-(U1-PXD1-PadA5)") (class "Default")
      (node (ref "U1") (pin "A5") (pinfunction "PXD1_A5") (pintype "passive+no_connect"))
    )
    (net (code "62") (name "unconnected-(U1-PXD2-PadB5)") (class "Default")
      (node (ref "U1") (pin "B5") (pinfunction "PXD2_B5") (pintype "passive+no_connect"))
    )
    (net (code "63") (name "unconnected-(U1-PXD3-PadD5)") (class "Default")
      (node (ref "U1") (pin "D5") (pinfunction "PXD3_D5") (pintype "passive+no_connect"))
    )
    (net (code "64") (name "unconnected-(U1-VDD12_O-PadE6)") (class "Default")
      (node (ref "U1") (pin "E6") (pinfunction "VDD12_O_E6") (pintype "passive+no_connect"))
    )
    (net (code "65") (name "unconnected-(U1-VSYNC-PadE4)") (class "Default")
      (node (ref "U1") (pin "E4") (pinfunction "VSYNC_E4") (pintype "passive+no_connect"))
    )
    (net (code "66") (name "unconnected-(U3-NC-Pad4)") (class "Default")
      (node (ref "U3") (pin "4") (pinfunction "NC_4") (pintype "passive+no_connect"))
    )
  )
)
